# SensorManager.net
KiCad netlist of a schematic drawn in EAGLE
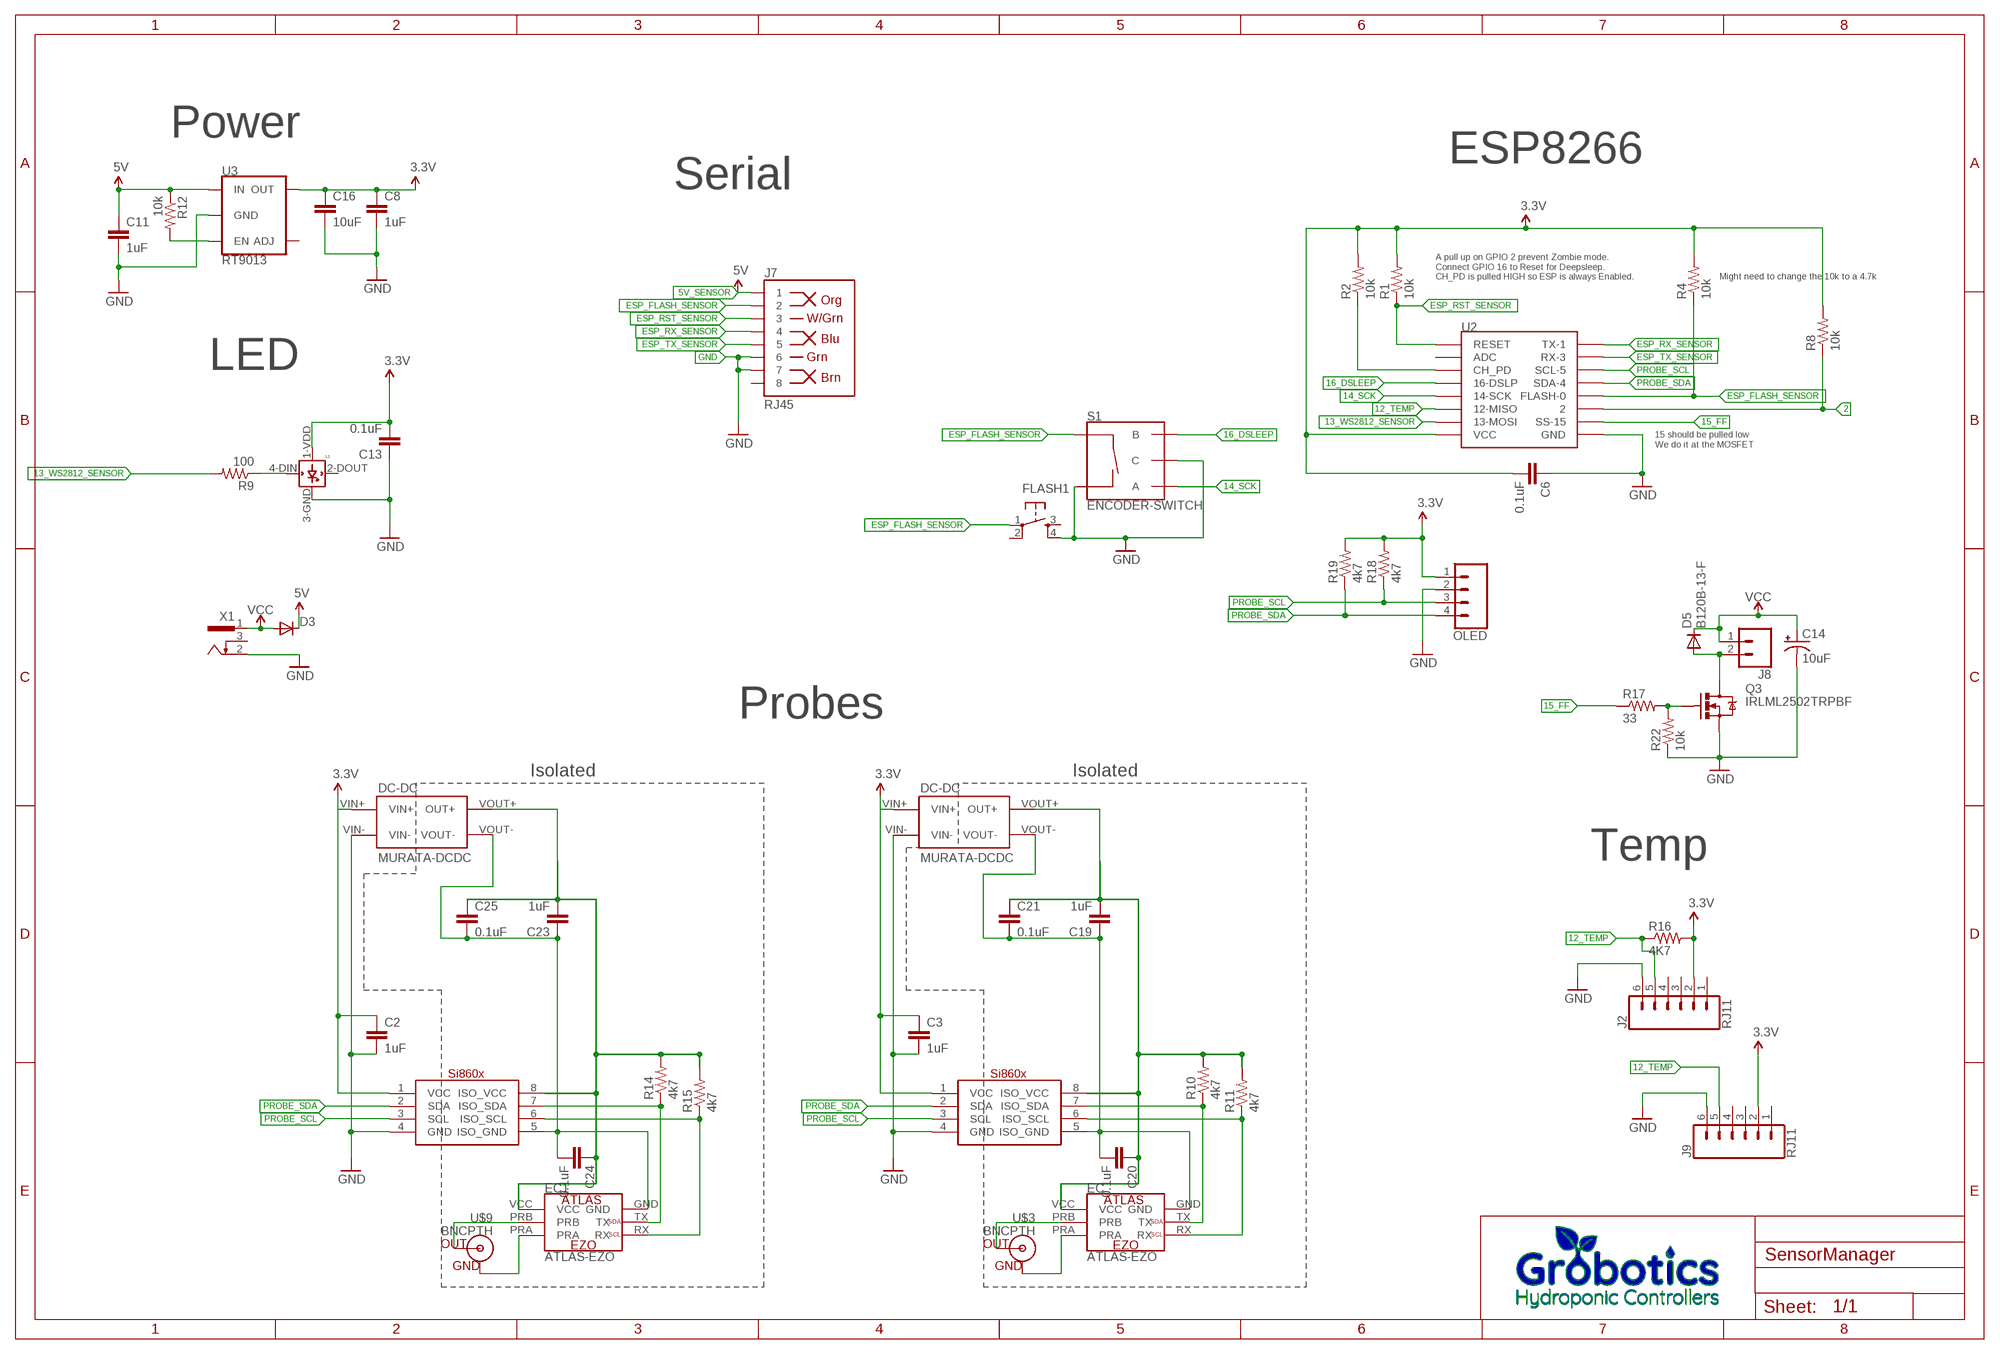
[diagram p0: schematic, sheet 1]

(export (version "E")
  (design (tool "Eeschema 10.0.6"))
  (components
    (comp (ref "C2")
      (value "1uF")
      (footprint "eagle-import:0805")
      (libsource (lib "eagle-import") (part "CAP0805"))
    )
    (comp (ref "C3")
      (value "1uF")
      (footprint "eagle-import:0805")
      (libsource (lib "eagle-import") (part "CAP0805"))
    )
    (comp (ref "C6")
      (value "0.1uF")
      (footprint "eagle-import:0805")
      (libsource (lib "eagle-import") (part "CAP0805"))
    )
    (comp (ref "C8")
      (value "1uF")
      (footprint "eagle-import:0805")
      (libsource (lib "eagle-import") (part "CAP0805"))
    )
    (comp (ref "C11")
      (value "1uF")
      (footprint "eagle-import:0805")
      (libsource (lib "eagle-import") (part "CAP0805"))
    )
    (comp (ref "C13")
      (value "0.1uF")
      (footprint "eagle-import:0805")
      (libsource (lib "eagle-import") (part "CAP0805"))
    )
    (comp (ref "C14")
      (value "10uF")
      (footprint "eagle-import:153CLV-0405")
      (libsource (lib "eagle-import") (part "CPOL-US153CLV-0405"))
    )
    (comp (ref "C16")
      (value "10uF")
      (footprint "eagle-import:0805")
      (libsource (lib "eagle-import") (part "CAP0805"))
    )
    (comp (ref "C19")
      (value "1uF")
      (footprint "eagle-import:0805")
      (libsource (lib "eagle-import") (part "CAP0805"))
    )
    (comp (ref "C20")
      (value "0.1uF")
      (footprint "eagle-import:0805")
      (libsource (lib "eagle-import") (part "CAP0805"))
    )
    (comp (ref "C21")
      (value "0.1uF")
      (footprint "eagle-import:0805")
      (libsource (lib "eagle-import") (part "CAP0805"))
    )
    (comp (ref "C23")
      (value "1uF")
      (footprint "eagle-import:0805")
      (libsource (lib "eagle-import") (part "CAP0805"))
    )
    (comp (ref "C24")
      (value "0.1uF")
      (footprint "eagle-import:0805")
      (libsource (lib "eagle-import") (part "CAP0805"))
    )
    (comp (ref "C25")
      (value "0.1uF")
      (footprint "eagle-import:0805")
      (libsource (lib "eagle-import") (part "CAP0805"))
    )
    (comp (ref "D3")
      (value "DIODESOD")
      (footprint "eagle-import:SOD-323")
      (libsource (lib "eagle-import") (part "DIODESOD"))
    )
    (comp (ref "D5")
      (value "B120B-13-F")
      (footprint "eagle-import:SMB-DIODE")
      (libsource (lib "eagle-import") (part "DIODESMB"))
    )
    (comp (ref "EC")
      (value "ATLAS-EZO")
      (footprint "eagle-import:ATLAS-EZO")
      (libsource (lib "eagle-import") (part "ATLAS-EZO"))
    )
    (comp (ref "EC1")
      (value "ATLAS-EZO")
      (footprint "eagle-import:ATLAS-EZO")
      (libsource (lib "eagle-import") (part "ATLAS-EZO"))
    )
    (comp (ref "FLASH1")
      (value "TAC_SWITCHSMD")
      (footprint "eagle-import:TACTILE_SWITCH_SMD")
      (libsource (lib "eagle-import") (part "TAC_SWITCHSMD"))
    )
    (comp (ref "J2")
      (value "RJ11")
      (footprint "eagle-import:RJ11-6")
      (libsource (lib "eagle-import") (part "RJ11-6"))
    )
    (comp (ref "J7")
      (value "RJ45")
      (footprint "eagle-import:RJ45-8")
      (libsource (lib "eagle-import") (part "RJ45-8"))
    )
    (comp (ref "J8")
      (value "CONN_02")
      (footprint "eagle-import:1X02")
      (libsource (lib "eagle-import") (part "CONN_02"))
    )
    (comp (ref "J9")
      (value "RJ11")
      (footprint "eagle-import:RJ11-6")
      (libsource (lib "eagle-import") (part "RJ11-6"))
    )
    (comp (ref "L1")
      (value "WS2812B")
      (footprint "eagle-import:WS2812B")
      (libsource (lib "eagle-import") (part "WS2812B"))
    )
    (comp (ref "OLED")
      (value "CONN_04")
      (footprint "eagle-import:1X04")
      (libsource (lib "eagle-import") (part "CONN_04"))
    )
    (comp (ref "Q3")
      (value "IRLML2502TRPBF")
      (footprint "eagle-import:SOT23-3")
      (libsource (lib "eagle-import") (part "MOSFET-NCHANNELSMD"))
    )
    (comp (ref "R1")
      (value "10k")
      (footprint "eagle-import:0805")
      (libsource (lib "eagle-import") (part "RESISTOR0805"))
    )
    (comp (ref "R2")
      (value "10k")
      (footprint "eagle-import:0805")
      (libsource (lib "eagle-import") (part "RESISTOR0805"))
    )
    (comp (ref "R4")
      (value "10k")
      (footprint "eagle-import:0805")
      (libsource (lib "eagle-import") (part "RESISTOR0805"))
    )
    (comp (ref "R8")
      (value "10k")
      (footprint "eagle-import:0805")
      (libsource (lib "eagle-import") (part "RESISTOR0805"))
    )
    (comp (ref "R9")
      (value "100")
      (footprint "eagle-import:0805")
      (libsource (lib "eagle-import") (part "RESISTOR0805"))
    )
    (comp (ref "R10")
      (value "4k7")
      (footprint "eagle-import:0805")
      (libsource (lib "eagle-import") (part "SparkFun-Resistors_RESISTOR0805-RES"))
    )
    (comp (ref "R11")
      (value "4k7")
      (footprint "eagle-import:0805")
      (libsource (lib "eagle-import") (part "SparkFun-Resistors_RESISTOR0805-RES"))
    )
    (comp (ref "R12")
      (value "10k")
      (footprint "eagle-import:0805")
      (libsource (lib "eagle-import") (part "RESISTOR0805"))
    )
    (comp (ref "R14")
      (value "4k7")
      (footprint "eagle-import:0805")
      (libsource (lib "eagle-import") (part "SparkFun-Resistors_RESISTOR0805-RES"))
    )
    (comp (ref "R15")
      (value "4k7")
      (footprint "eagle-import:0805")
      (libsource (lib "eagle-import") (part "SparkFun-Resistors_RESISTOR0805-RES"))
    )
    (comp (ref "R16")
      (value "4K7")
      (footprint "eagle-import:0805")
      (libsource (lib "eagle-import") (part "SparkFun-Resistors_RESISTOR0805-RES"))
    )
    (comp (ref "R17")
      (value "33")
      (footprint "eagle-import:0805")
      (libsource (lib "eagle-import") (part "RESISTOR0805"))
    )
    (comp (ref "R18")
      (value "4k7")
      (footprint "eagle-import:0805")
      (libsource (lib "eagle-import") (part "RESISTOR0805"))
    )
    (comp (ref "R19")
      (value "4k7")
      (footprint "eagle-import:0805")
      (libsource (lib "eagle-import") (part "RESISTOR0805"))
    )
    (comp (ref "R22")
      (value "10k")
      (footprint "eagle-import:0805")
      (libsource (lib "eagle-import") (part "RESISTOR0805"))
    )
    (comp (ref "S1")
      (value "ENCODER-SWITCH")
      (footprint "eagle-import:ROTARY_ENC_PLAIN")
      (libsource (lib "eagle-import") (part "ENCODER-SWITCH"))
    )
    (comp (ref "U$3")
      (value "BNCPTH")
      (footprint "eagle-import:BNC")
      (libsource (lib "eagle-import") (part "BNCPTH"))
    )
    (comp (ref "U$4")
      (value "MURATA-DCDC")
      (footprint "eagle-import:MURATA_DCDC")
      (libsource (lib "eagle-import") (part "MURATA-DCDC"))
    )
    (comp (ref "U$8")
      (value "SI860X")
      (footprint "eagle-import:SO08")
      (libsource (lib "eagle-import") (part "SI860X"))
    )
    (comp (ref "U$9")
      (value "BNCPTH")
      (footprint "eagle-import:BNC")
      (libsource (lib "eagle-import") (part "BNCPTH"))
    )
    (comp (ref "U$11")
      (value "SI860X")
      (footprint "eagle-import:SO08")
      (libsource (lib "eagle-import") (part "SI860X"))
    )
    (comp (ref "U$12")
      (value "LOGO_GROBOTICS")
      (footprint "eagle-import:GROBOTICS")
      (libsource (lib "eagle-import") (part "LOGO_GROBOTICS"))
    )
    (comp (ref "U$14")
      (value "MURATA-DCDC")
      (footprint "eagle-import:MURATA_DCDC")
      (libsource (lib "eagle-import") (part "MURATA-DCDC"))
    )
    (comp (ref "U2")
      (value "ESP12SMD")
      (footprint "eagle-import:ESP12-SMD")
      (libsource (lib "eagle-import") (part "ESP12SMD"))
    )
    (comp (ref "U3")
      (value "RT9013")
      (footprint "eagle-import:SOT23-5")
      (libsource (lib "eagle-import") (part "AP2202-ADJ"))
    )
    (comp (ref "X1")
      (value "733980-62")
      (footprint "eagle-import:733980-62")
      (libsource (lib "eagle-import") (part "73398?0-62"))
    )
  )
  (nets
    (net (code "1") (name "2") (class "Default")
      (node (ref "R8") (pin "1") (pinfunction "1_1") (pintype "passive"))
      (node (ref "U2") (pin "GPIO2") (pinfunction "2_GPIO2") (pintype "bidirectional"))
    )
    (net (code "2") (name "3.3V") (class "Default")
      (node (ref "C13") (pin "2") (pinfunction "2_2") (pintype "passive"))
      (node (ref "C16") (pin "1") (pinfunction "1_1") (pintype "passive"))
      (node (ref "C2") (pin "1") (pinfunction "1_1") (pintype "passive"))
      (node (ref "C3") (pin "1") (pinfunction "1_1") (pintype "passive"))
      (node (ref "C6") (pin "2") (pinfunction "2_2") (pintype "passive"))
      (node (ref "C8") (pin "1") (pinfunction "1_1") (pintype "passive"))
      (node (ref "J2") (pin "2") (pinfunction "2_2") (pintype "passive"))
      (node (ref "J9") (pin "2") (pinfunction "2_2") (pintype "passive"))
      (node (ref "L1") (pin "1-VDD") (pinfunction "VDD_1-VDD") (pintype "bidirectional"))
      (node (ref "OLED") (pin "1") (pinfunction "1_1") (pintype "passive"))
      (node (ref "R1") (pin "2") (pinfunction "2_2") (pintype "passive"))
      (node (ref "R16") (pin "2") (pinfunction "2_2") (pintype "passive"))
      (node (ref "R18") (pin "2") (pinfunction "2_2") (pintype "passive"))
      (node (ref "R19") (pin "2") (pinfunction "2_2") (pintype "passive"))
      (node (ref "R2") (pin "2") (pinfunction "2_2") (pintype "passive"))
      (node (ref "R4") (pin "2") (pinfunction "2_2") (pintype "passive"))
      (node (ref "R8") (pin "2") (pinfunction "2_2") (pintype "passive"))
      (node (ref "U$11") (pin "1") (pinfunction "VCC_1") (pintype "bidirectional"))
      (node (ref "U$14") (pin "VIN+") (pinfunction "VIN+_VIN+") (pintype "bidirectional"))
      (node (ref "U$4") (pin "VIN+") (pinfunction "VIN+_VIN+") (pintype "bidirectional"))
      (node (ref "U$8") (pin "1") (pinfunction "VCC_1") (pintype "bidirectional"))
      (node (ref "U2") (pin "VCC") (pinfunction "VCC_VCC") (pintype "bidirectional"))
      (node (ref "U3") (pin "5") (pinfunction "OUT_5") (pintype "passive"))
    )
    (net (code "3") (name "5V_SENSOR") (class "Default")
      (node (ref "C11") (pin "1") (pinfunction "1_1") (pintype "passive"))
      (node (ref "D3") (pin "1") (pinfunction "C_1") (pintype "passive"))
      (node (ref "J7") (pin "1") (pinfunction "1_1") (pintype "bidirectional"))
      (node (ref "R12") (pin "1") (pinfunction "1_1") (pintype "passive"))
      (node (ref "U3") (pin "1") (pinfunction "IN_1") (pintype "input"))
    )
    (net (code "4") (name "12_TEMP") (class "Default")
      (node (ref "J2") (pin "5") (pinfunction "5_5") (pintype "passive"))
      (node (ref "J9") (pin "5") (pinfunction "5_5") (pintype "passive"))
      (node (ref "R16") (pin "1") (pinfunction "1_1") (pintype "passive"))
      (node (ref "U2") (pin "GPIO12") (pinfunction "12-MISO_GPIO12") (pintype "bidirectional"))
    )
    (net (code "5") (name "13_WS2812_SENSOR") (class "Default")
      (node (ref "R9") (pin "2") (pinfunction "2_2") (pintype "passive"))
      (node (ref "U2") (pin "GPIO13") (pinfunction "13-MOSI_GPIO13") (pintype "bidirectional"))
    )
    (net (code "6") (name "14_SCK") (class "Default")
      (node (ref "S1") (pin "A") (pinfunction "A_A") (pintype "bidirectional"))
      (node (ref "U2") (pin "GPIO14") (pinfunction "14-SCK_GPIO14") (pintype "bidirectional"))
    )
    (net (code "7") (name "15_FF") (class "Default")
      (node (ref "R17") (pin "1") (pinfunction "1_1") (pintype "passive"))
      (node (ref "U2") (pin "GPIO15") (pinfunction "SS-15_GPIO15") (pintype "bidirectional"))
    )
    (net (code "8") (name "16_DSLEEP") (class "Default")
      (node (ref "S1") (pin "B") (pinfunction "B_B") (pintype "bidirectional"))
      (node (ref "U2") (pin "GPIO16") (pinfunction "16-DSLP_GPIO16") (pintype "bidirectional"))
    )
    (net (code "9") (name "ESP_FLASH_SENSOR") (class "Default")
      (node (ref "FLASH1") (pin "1") (pinfunction "1_1") (pintype "passive"))
      (node (ref "J7") (pin "2") (pinfunction "2_2") (pintype "bidirectional"))
      (node (ref "R4") (pin "1") (pinfunction "1_1") (pintype "passive"))
      (node (ref "S1") (pin "SW+") (pinfunction "SW+_SW+") (pintype "bidirectional"))
      (node (ref "U2") (pin "GPIO0") (pinfunction "FLASH-0_GPIO0") (pintype "bidirectional"))
    )
    (net (code "10") (name "ESP_RST_SENSOR") (class "Default")
      (node (ref "J7") (pin "3") (pinfunction "3_3") (pintype "bidirectional"))
      (node (ref "R1") (pin "1") (pinfunction "1_1") (pintype "passive"))
      (node (ref "U2") (pin "RESET") (pinfunction "RESET_RESET") (pintype "bidirectional"))
    )
    (net (code "11") (name "ESP_RX_SENSOR") (class "Default")
      (node (ref "J7") (pin "4") (pinfunction "4_4") (pintype "bidirectional"))
      (node (ref "U2") (pin "TXD0") (pinfunction "TX-1_TXD0") (pintype "bidirectional"))
    )
    (net (code "12") (name "ESP_TX_SENSOR") (class "Default")
      (node (ref "J7") (pin "5") (pinfunction "5_5") (pintype "bidirectional"))
      (node (ref "U2") (pin "RXD0") (pinfunction "RX-3_RXD0") (pintype "bidirectional"))
    )
    (net (code "13") (name "GND") (class "Default")
      (node (ref "C11") (pin "2") (pinfunction "2_2") (pintype "passive"))
      (node (ref "C13") (pin "1") (pinfunction "1_1") (pintype "passive"))
      (node (ref "C14") (pin "-") (pinfunction "-_-") (pintype "passive"))
      (node (ref "C16") (pin "2") (pinfunction "2_2") (pintype "passive"))
      (node (ref "C2") (pin "2") (pinfunction "2_2") (pintype "passive"))
      (node (ref "C3") (pin "2") (pinfunction "2_2") (pintype "passive"))
      (node (ref "C6") (pin "1") (pinfunction "1_1") (pintype "passive"))
      (node (ref "C8") (pin "2") (pinfunction "2_2") (pintype "passive"))
      (node (ref "FLASH1") (pin "4") (pinfunction "4_4") (pintype "passive"))
      (node (ref "J2") (pin "6") (pinfunction "6_6") (pintype "passive"))
      (node (ref "J7") (pin "6") (pinfunction "6_6") (pintype "bidirectional"))
      (node (ref "J7") (pin "7") (pinfunction "7_7") (pintype "bidirectional"))
      (node (ref "J9") (pin "6") (pinfunction "6_6") (pintype "passive"))
      (node (ref "L1") (pin "3-GND") (pinfunction "GND_3-GND") (pintype "bidirectional"))
      (node (ref "OLED") (pin "2") (pinfunction "2_2") (pintype "passive"))
      (node (ref "Q3") (pin "2") (pinfunction "S_2") (pintype "passive"))
      (node (ref "R22") (pin "1") (pinfunction "1_1") (pintype "passive"))
      (node (ref "S1") (pin "C") (pinfunction "C_C") (pintype "bidirectional"))
      (node (ref "S1") (pin "SW-") (pinfunction "SW-_SW-") (pintype "bidirectional"))
      (node (ref "U$11") (pin "4") (pinfunction "GND_4") (pintype "bidirectional"))
      (node (ref "U$14") (pin "VIN-") (pinfunction "VIN-_VIN-") (pintype "bidirectional"))
      (node (ref "U$4") (pin "VIN-") (pinfunction "VIN-_VIN-") (pintype "bidirectional"))
      (node (ref "U$8") (pin "4") (pinfunction "GND_4") (pintype "bidirectional"))
      (node (ref "U2") (pin "GND") (pinfunction "GND_GND") (pintype "bidirectional"))
      (node (ref "U3") (pin "2") (pinfunction "GND_2") (pintype "input"))
      (node (ref "X1") (pin "2") (pinfunction "2_2") (pintype "passive"))
    )
    (net (code "14") (name "Net-(EC-PadPRA)") (class "Default")
      (node (ref "EC") (pin "PRA") (pinfunction "PRA_PRA") (pintype "bidirectional"))
      (node (ref "U$3") (pin "GND") (pinfunction "GND_GND") (pintype "bidirectional"))
    )
    (net (code "15") (name "Net-(EC1-PadPRA)") (class "Default")
      (node (ref "EC1") (pin "PRA") (pinfunction "PRA_PRA") (pintype "bidirectional"))
      (node (ref "U$9") (pin "GND") (pinfunction "GND_GND") (pintype "bidirectional"))
    )
    (net (code "16") (name "Net-(L1-DIN)") (class "Default")
      (node (ref "L1") (pin "4-DIN") (pinfunction "DIN_4-DIN") (pintype "input"))
      (node (ref "R9") (pin "1") (pinfunction "1_1") (pintype "passive"))
    )
    (net (code "17") (name "Net-(Q3-D)") (class "Default")
      (node (ref "D5") (pin "A") (pinfunction "A_A") (pintype "passive"))
      (node (ref "J8") (pin "2") (pinfunction "2_2") (pintype "passive"))
      (node (ref "Q3") (pin "3") (pinfunction "D_3") (pintype "passive"))
    )
    (net (code "18") (name "Net-(Q3-G)") (class "Default")
      (node (ref "Q3") (pin "1") (pinfunction "G_1") (pintype "passive"))
      (node (ref "R17") (pin "2") (pinfunction "2_2") (pintype "passive"))
      (node (ref "R22") (pin "2") (pinfunction "2_2") (pintype "passive"))
    )
    (net (code "19") (name "Net-(R2-Pad1)") (class "Default")
      (node (ref "R2") (pin "1") (pinfunction "1_1") (pintype "passive"))
      (node (ref "U2") (pin "CH_PD") (pinfunction "CH_PD_CH_PD") (pintype "bidirectional"))
    )
    (net (code "20") (name "Net-(U$3-OUT)") (class "Default")
      (node (ref "EC") (pin "PRB") (pinfunction "PRB_PRB") (pintype "bidirectional"))
      (node (ref "U$3") (pin "S") (pinfunction "OUT_S") (pintype "bidirectional"))
    )
    (net (code "21") (name "Net-(U$4-OUT+)") (class "Default")
      (node (ref "C19") (pin "2") (pinfunction "2_2") (pintype "passive"))
      (node (ref "C20") (pin "1") (pinfunction "1_1") (pintype "passive"))
      (node (ref "C21") (pin "1") (pinfunction "1_1") (pintype "passive"))
      (node (ref "EC") (pin "VCC") (pinfunction "VCC_VCC") (pintype "bidirectional"))
      (node (ref "R10") (pin "2") (pinfunction "2_2") (pintype "passive"))
      (node (ref "R11") (pin "2") (pinfunction "2_2") (pintype "passive"))
      (node (ref "U$4") (pin "VOUT+") (pinfunction "OUT+_VOUT+") (pintype "bidirectional"))
      (node (ref "U$8") (pin "8") (pinfunction "ISO_VCC_8") (pintype "bidirectional"))
    )
    (net (code "22") (name "Net-(U$8-ISO_GND)") (class "Default")
      (node (ref "C19") (pin "1") (pinfunction "1_1") (pintype "passive"))
      (node (ref "C20") (pin "2") (pinfunction "2_2") (pintype "passive"))
      (node (ref "C21") (pin "2") (pinfunction "2_2") (pintype "passive"))
      (node (ref "EC") (pin "GND") (pinfunction "GND_GND") (pintype "bidirectional"))
      (node (ref "U$4") (pin "VOUT-") (pinfunction "VOUT-_VOUT-") (pintype "bidirectional"))
      (node (ref "U$8") (pin "5") (pinfunction "ISO_GND_5") (pintype "bidirectional"))
    )
    (net (code "23") (name "Net-(U$8-ISO_SCL)") (class "Default")
      (node (ref "EC") (pin "RX") (pinfunction "RX_RX") (pintype "bidirectional"))
      (node (ref "R11") (pin "1") (pinfunction "1_1") (pintype "passive"))
      (node (ref "U$8") (pin "6") (pinfunction "ISO_SCL_6") (pintype "bidirectional"))
    )
    (net (code "24") (name "Net-(U$8-ISO_SDA)") (class "Default")
      (node (ref "EC") (pin "TX") (pinfunction "TX_TX") (pintype "bidirectional"))
      (node (ref "R10") (pin "1") (pinfunction "1_1") (pintype "passive"))
      (node (ref "U$8") (pin "7") (pinfunction "ISO_SDA_7") (pintype "bidirectional"))
    )
    (net (code "25") (name "Net-(U$9-OUT)") (class "Default")
      (node (ref "EC1") (pin "PRB") (pinfunction "PRB_PRB") (pintype "bidirectional"))
      (node (ref "U$9") (pin "S") (pinfunction "OUT_S") (pintype "bidirectional"))
    )
    (net (code "26") (name "Net-(U$11-ISO_GND)") (class "Default")
      (node (ref "C23") (pin "1") (pinfunction "1_1") (pintype "passive"))
      (node (ref "C24") (pin "2") (pinfunction "2_2") (pintype "passive"))
      (node (ref "C25") (pin "2") (pinfunction "2_2") (pintype "passive"))
      (node (ref "EC1") (pin "GND") (pinfunction "GND_GND") (pintype "bidirectional"))
      (node (ref "U$11") (pin "5") (pinfunction "ISO_GND_5") (pintype "bidirectional"))
      (node (ref "U$14") (pin "VOUT-") (pinfunction "VOUT-_VOUT-") (pintype "bidirectional"))
    )
    (net (code "27") (name "Net-(U$11-ISO_SCL)") (class "Default")
      (node (ref "EC1") (pin "RX") (pinfunction "RX_RX") (pintype "bidirectional"))
      (node (ref "R15") (pin "1") (pinfunction "1_1") (pintype "passive"))
      (node (ref "U$11") (pin "6") (pinfunction "ISO_SCL_6") (pintype "bidirectional"))
    )
    (net (code "28") (name "Net-(U$11-ISO_SDA)") (class "Default")
      (node (ref "EC1") (pin "TX") (pinfunction "TX_TX") (pintype "bidirectional"))
      (node (ref "R14") (pin "1") (pinfunction "1_1") (pintype "passive"))
      (node (ref "U$11") (pin "7") (pinfunction "ISO_SDA_7") (pintype "bidirectional"))
    )
    (net (code "29") (name "Net-(U$11-ISO_VCC)") (class "Default")
      (node (ref "C23") (pin "2") (pinfunction "2_2") (pintype "passive"))
      (node (ref "C24") (pin "1") (pinfunction "1_1") (pintype "passive"))
      (node (ref "C25") (pin "1") (pinfunction "1_1") (pintype "passive"))
      (node (ref "EC1") (pin "VCC") (pinfunction "VCC_VCC") (pintype "bidirectional"))
      (node (ref "R14") (pin "2") (pinfunction "2_2") (pintype "passive"))
      (node (ref "R15") (pin "2") (pinfunction "2_2") (pintype "passive"))
      (node (ref "U$11") (pin "8") (pinfunction "ISO_VCC_8") (pintype "bidirectional"))
      (node (ref "U$14") (pin "VOUT+") (pinfunction "OUT+_VOUT+") (pintype "bidirectional"))
    )
    (net (code "30") (name "Net-(U3-EN)") (class "Default")
      (node (ref "R12") (pin "2") (pinfunction "2_2") (pintype "passive"))
      (node (ref "U3") (pin "3") (pinfunction "EN_3") (pintype "input"))
    )
    (net (code "31") (name "PROBE_SCL") (class "Default")
      (node (ref "OLED") (pin "3") (pinfunction "3_3") (pintype "passive"))
      (node (ref "R18") (pin "1") (pinfunction "1_1") (pintype "passive"))
      (node (ref "U$11") (pin "3") (pinfunction "SCL_3") (pintype "bidirectional"))
      (node (ref "U$8") (pin "3") (pinfunction "SCL_3") (pintype "bidirectional"))
      (node (ref "U2") (pin "GPIO5") (pinfunction "SCL-5_GPIO5") (pintype "bidirectional"))
    )
    (net (code "32") (name "PROBE_SDA") (class "Default")
      (node (ref "OLED") (pin "4") (pinfunction "4_4") (pintype "passive"))
      (node (ref "R19") (pin "1") (pinfunction "1_1") (pintype "passive"))
      (node (ref "U$11") (pin "2") (pinfunction "SDA_2") (pintype "bidirectional"))
      (node (ref "U$8") (pin "2") (pinfunction "SDA_2") (pintype "bidirectional"))
      (node (ref "U2") (pin "GPIO4") (pinfunction "SDA-4_GPIO4") (pintype "bidirectional"))
    )
    (net (code "33") (name "VCC") (class "Default")
      (node (ref "C14") (pin "+") (pinfunction "+_+") (pintype "passive"))
      (node (ref "D3") (pin "2") (pinfunction "A_2") (pintype "passive"))
      (node (ref "D5") (pin "C") (pinfunction "C_C") (pintype "passive"))
      (node (ref "J8") (pin "1") (pinfunction "1_1") (pintype "passive"))
      (node (ref "X1") (pin "1") (pinfunction "1_1") (pintype "passive"))
    )
    (net (code "34") (name "unconnected-(FLASH1-Pad2)") (class "Default")
      (node (ref "FLASH1") (pin "2") (pinfunction "2_2") (pintype "passive"))
    )
    (net (code "35") (name "unconnected-(FLASH1-Pad3)") (class "Default")
      (node (ref "FLASH1") (pin "3") (pinfunction "3_3") (pintype "passive"))
    )
    (net (code "36") (name "unconnected-(J2-Pad1)") (class "Default")
      (node (ref "J2") (pin "1") (pinfunction "1_1") (pintype "passive"))
    )
    (net (code "37") (name "unconnected-(J2-Pad3)") (class "Default")
      (node (ref "J2") (pin "3") (pinfunction "3_3") (pintype "passive"))
    )
    (net (code "38") (name "unconnected-(J2-Pad4)") (class "Default")
      (node (ref "J2") (pin "4") (pinfunction "4_4") (pintype "passive"))
    )
    (net (code "39") (name "unconnected-(J7-Pad8)") (class "Default")
      (node (ref "J7") (pin "8") (pinfunction "8_8") (pintype "bidirectional"))
    )
    (net (code "40") (name "unconnected-(J9-Pad1)") (class "Default")
      (node (ref "J9") (pin "1") (pinfunction "1_1") (pintype "passive"))
    )
    (net (code "41") (name "unconnected-(J9-Pad3)") (class "Default")
      (node (ref "J9") (pin "3") (pinfunction "3_3") (pintype "passive"))
    )
    (net (code "42") (name "unconnected-(J9-Pad4)") (class "Default")
      (node (ref "J9") (pin "4") (pinfunction "4_4") (pintype "passive"))
    )
    (net (code "43") (name "unconnected-(L1-DOUT-Pad2-DOUT)") (class "Default")
      (node (ref "L1") (pin "2-DOUT") (pinfunction "DOUT_2-DOUT") (pintype "output"))
    )
    (net (code "44") (name "unconnected-(U2-PadADC)") (class "Default")
      (node (ref "U2") (pin "ADC") (pinfunction "ADC_ADC") (pintype "bidirectional"))
    )
    (net (code "45") (name "unconnected-(U3-ADJ-Pad4)") (class "Default")
      (node (ref "U3") (pin "4") (pinfunction "ADJ_4") (pintype "input"))
    )
    (net (code "46") (name "unconnected-(X1-Pad3)") (class "Default")
      (node (ref "X1") (pin "3") (pinfunction "3_3") (pintype "passive"))
    )
  )
)
